# layout.net
KiCad netlist of a schematic drawn in EAGLE
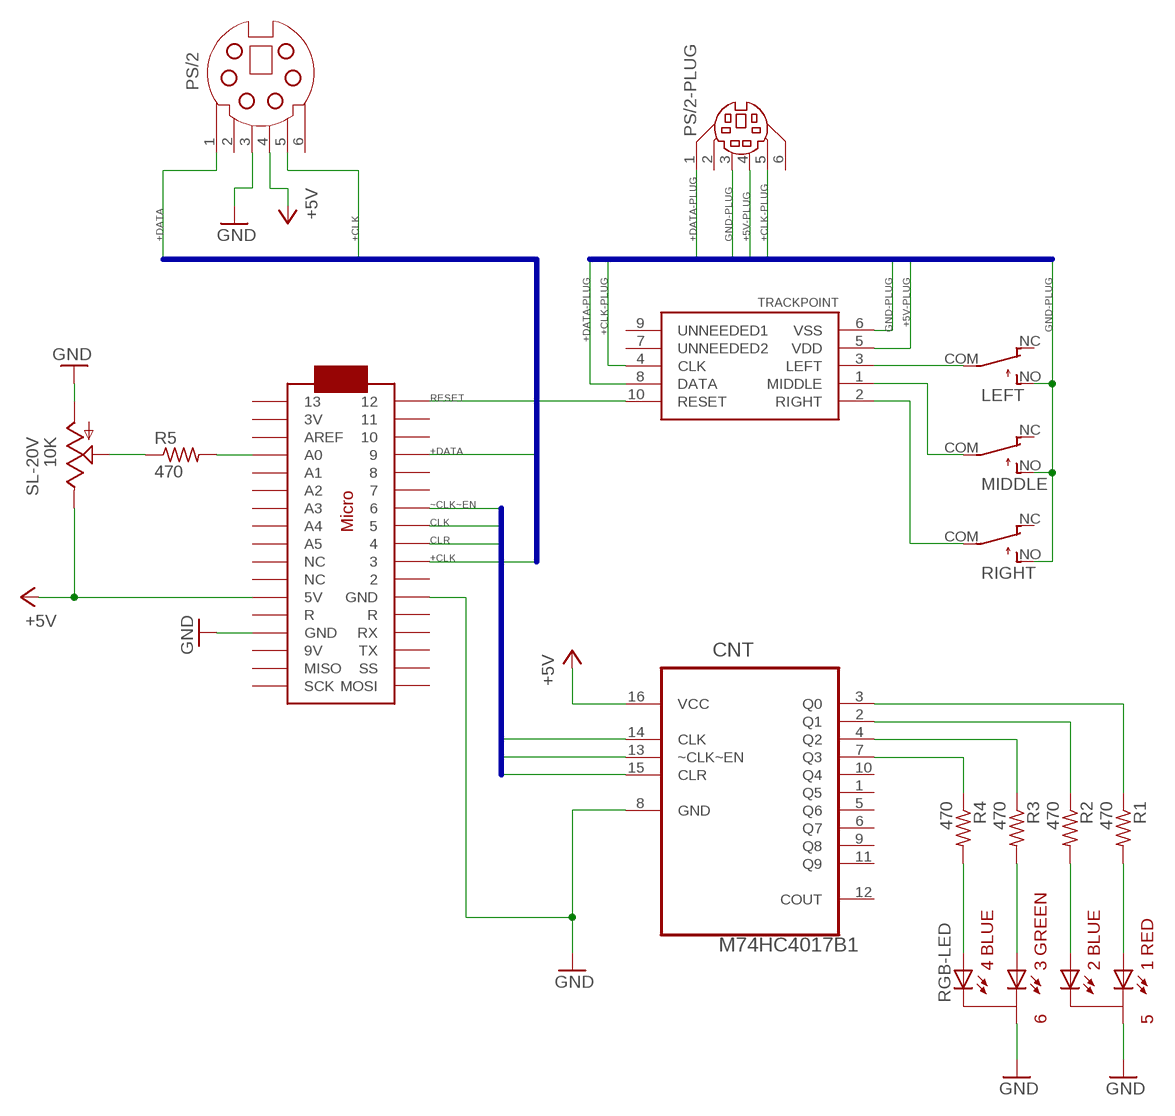
[diagram p0: schematic, sheet 1]

(export (version "E")
  (design (tool "Eeschema 10.0.6"))
  (components
    (comp (ref "CNT")
      (value "M74HC4017B1")
      (footprint "eagle-import:DIP254P762X510-16")
      (fields (field (name "MPN") "M74HC4017B1R"))
      (libsource (lib "eagle-import") (part "M74HC4017B1R"))
    )
    (comp (ref "PS/2")
      (value "MDSSV-BC06")
      (footprint "eagle-import:SSV-BC06")
      (libsource (lib "eagle-import") (part "MDSSV-BC06"))
    )
    (comp (ref "PS/2-PLUG")
      (value "MDIN06K")
      (footprint "eagle-import:MDIN06K")
      (libsource (lib "eagle-import") (part "MDIN06K"))
    )
    (comp (ref "R1")
      (value "470")
      (footprint "eagle-import:0207_10")
      (libsource (lib "eagle-import") (part "R-US_0207/10"))
    )
    (comp (ref "R2")
      (value "470")
      (footprint "eagle-import:0207_10")
      (libsource (lib "eagle-import") (part "R-US_0207/10"))
    )
    (comp (ref "R3")
      (value "470")
      (footprint "eagle-import:0207_10")
      (libsource (lib "eagle-import") (part "R-US_0207/10"))
    )
    (comp (ref "R4")
      (value "470")
      (footprint "eagle-import:0207_10")
      (libsource (lib "eagle-import") (part "R-US_0207/10"))
    )
    (comp (ref "R5")
      (value "470")
      (footprint "eagle-import:0207_10")
      (libsource (lib "eagle-import") (part "R-US_0207/10"))
    )
    (comp (ref "RGB-LED")
      (value "RGBLED")
      (footprint "eagle-import:RGBLED5MM")
      (libsource (lib "eagle-import") (part "RGBLED"))
    )
    (comp (ref "TRACKPOINT")
      (value "BOARD")
      (footprint "eagle-import:BOARD")
      (libsource (lib "eagle-import") (part "BOARD"))
    )
    (comp (ref "U$1")
      (value "LEFT")
      (footprint "eagle-import:D2F")
      (libsource (lib "eagle-import") (part "D2F"))
    )
    (comp (ref "U$2")
      (value "ARDUINOMICRO")
      (footprint "eagle-import:ARDUINOMICRO")
      (libsource (lib "eagle-import") (part "ARDUINOMICRO"))
    )
    (comp (ref "U$3")
      (value "MIDDLE")
      (footprint "eagle-import:D2F")
      (libsource (lib "eagle-import") (part "D2F"))
    )
    (comp (ref "U$5")
      (value "RIGHT")
      (footprint "eagle-import:D2F")
      (libsource (lib "eagle-import") (part "D2F"))
    )
    (comp (ref "U$6")
      (value "10K")
      (footprint "eagle-import:SL-20V")
      (libsource (lib "eagle-import") (part "SL-20V"))
    )
  )
  (nets
    (net (code "1") (name "+5V") (class "Default")
      (node (ref "CNT") (pin "16") (pinfunction "VCC_16") (pintype "power_in"))
      (node (ref "PS/2") (pin "4") (pinfunction "4_4") (pintype "passive"))
      (node (ref "U$2") (pin "P$23") (pinfunction "5V_P$23") (pintype "bidirectional"))
      (node (ref "U$6") (pin "4") (pinfunction "E_4") (pintype "passive"))
    )
    (net (code "2") (name "/+5V-PLUG") (class "Default")
      (node (ref "PS/2-PLUG") (pin "4") (pinfunction "4_4") (pintype "passive"))
      (node (ref "TRACKPOINT") (pin "5") (pinfunction "VDD_5") (pintype "bidirectional"))
    )
    (net (code "3") (name "/+CLK") (class "Default")
      (node (ref "PS/2") (pin "5") (pinfunction "5_5") (pintype "passive"))
      (node (ref "U$2") (pin "P$10") (pinfunction "3_P$10") (pintype "bidirectional"))
    )
    (net (code "4") (name "/+CLK-PLUG") (class "Default")
      (node (ref "PS/2-PLUG") (pin "5") (pinfunction "5_5") (pintype "passive"))
      (node (ref "TRACKPOINT") (pin "4") (pinfunction "CLK_4") (pintype "bidirectional"))
    )
    (net (code "5") (name "/+DATA") (class "Default")
      (node (ref "PS/2") (pin "1") (pinfunction "1_1") (pintype "passive"))
      (node (ref "U$2") (pin "P$4") (pinfunction "9_P$4") (pintype "bidirectional"))
    )
    (net (code "6") (name "/+DATA-PLUG") (class "Default")
      (node (ref "PS/2-PLUG") (pin "1") (pinfunction "1_1") (pintype "passive"))
      (node (ref "TRACKPOINT") (pin "8") (pinfunction "DATA_8") (pintype "bidirectional"))
    )
    (net (code "7") (name "/CLK") (class "Default")
      (node (ref "CNT") (pin "14") (pinfunction "CLK_14") (pintype "input"))
      (node (ref "U$2") (pin "P$8") (pinfunction "5_P$8") (pintype "bidirectional"))
    )
    (net (code "8") (name "/CLR") (class "Default")
      (node (ref "CNT") (pin "15") (pinfunction "CLR_15") (pintype "input"))
      (node (ref "U$2") (pin "P$9") (pinfunction "4_P$9") (pintype "bidirectional"))
    )
    (net (code "9") (name "/GND-PLUG") (class "Default")
      (node (ref "PS/2-PLUG") (pin "3") (pinfunction "3_3") (pintype "passive"))
      (node (ref "TRACKPOINT") (pin "6") (pinfunction "VSS_6") (pintype "bidirectional"))
      (node (ref "U$1") (pin "NO") (pinfunction "S_NO") (pintype "passive"))
      (node (ref "U$3") (pin "NO") (pinfunction "S_NO") (pintype "passive"))
      (node (ref "U$5") (pin "NO") (pinfunction "S_NO") (pintype "passive"))
    )
    (net (code "10") (name "/RESET") (class "Default")
      (node (ref "TRACKPOINT") (pin "10") (pinfunction "RESET_10") (pintype "bidirectional"))
      (node (ref "U$2") (pin "P$1") (pinfunction "12_P$1") (pintype "bidirectional"))
    )
    (net (code "11") (name "/~{CLK}EN") (class "Default")
      (node (ref "CNT") (pin "13") (pinfunction "~{CLK}EN_13") (pintype "input"))
      (node (ref "U$2") (pin "P$7") (pinfunction "6_P$7") (pintype "bidirectional"))
    )
    (net (code "12") (name "GND") (class "Default")
      (node (ref "CNT") (pin "8") (pinfunction "GND_8") (pintype "passive"))
      (node (ref "PS/2") (pin "3") (pinfunction "3_3") (pintype "passive"))
      (node (ref "RGB-LED") (pin "C5") (pinfunction "C5_C5") (pintype "passive"))
      (node (ref "RGB-LED") (pin "C6") (pinfunction "C6_C6") (pintype "passive"))
      (node (ref "U$2") (pin "P$12") (pinfunction "GND_P$12") (pintype "bidirectional"))
      (node (ref "U$2") (pin "P$21") (pinfunction "GND_P$21") (pintype "bidirectional"))
      (node (ref "U$6") (pin "1") (pinfunction "A_1") (pintype "passive"))
    )
    (net (code "13") (name "Net-(CNT-Q0)") (class "Default")
      (node (ref "CNT") (pin "3") (pinfunction "Q0_3") (pintype "output"))
      (node (ref "R1") (pin "1") (pinfunction "1_1") (pintype "passive"))
    )
    (net (code "14") (name "Net-(CNT-Q1)") (class "Default")
      (node (ref "CNT") (pin "2") (pinfunction "Q1_2") (pintype "output"))
      (node (ref "R2") (pin "1") (pinfunction "1_1") (pintype "passive"))
    )
    (net (code "15") (name "Net-(CNT-Q2)") (class "Default")
      (node (ref "CNT") (pin "4") (pinfunction "Q2_4") (pintype "output"))
      (node (ref "R3") (pin "1") (pinfunction "1_1") (pintype "passive"))
    )
    (net (code "16") (name "Net-(CNT-Q3)") (class "Default")
      (node (ref "CNT") (pin "7") (pinfunction "Q3_7") (pintype "output"))
      (node (ref "R4") (pin "1") (pinfunction "1_1") (pintype "passive"))
    )
    (net (code "17") (name "Net-(R1-Pad2)") (class "Default")
      (node (ref "R1") (pin "2") (pinfunction "2_2") (pintype "passive"))
      (node (ref "RGB-LED") (pin "A1_RED") (pinfunction "A1_RED_A1_RED") (pintype "passive"))
    )
    (net (code "18") (name "Net-(R2-Pad2)") (class "Default")
      (node (ref "R2") (pin "2") (pinfunction "2_2") (pintype "passive"))
      (node (ref "RGB-LED") (pin "A2_BLUE") (pinfunction "A2_BLUE_A2_BLUE") (pintype "passive"))
    )
    (net (code "19") (name "Net-(R3-Pad2)") (class "Default")
      (node (ref "R3") (pin "2") (pinfunction "2_2") (pintype "passive"))
      (node (ref "RGB-LED") (pin "A3_GREEN") (pinfunction "A3_GREEN_A3_GREEN") (pintype "passive"))
    )
    (net (code "20") (name "Net-(R4-Pad2)") (class "Default")
      (node (ref "R4") (pin "2") (pinfunction "2_2") (pintype "passive"))
      (node (ref "RGB-LED") (pin "A4_BLUE") (pinfunction "A4_BLUE_A4_BLUE") (pintype "passive"))
    )
    (net (code "21") (name "Net-(R5-Pad1)") (class "Default")
      (node (ref "R5") (pin "1") (pinfunction "1_1") (pintype "passive"))
      (node (ref "U$6") (pin "2") (pinfunction "S_2") (pintype "passive"))
      (node (ref "U$6") (pin "3") (pinfunction "S_3") (pintype "passive"))
    )
    (net (code "22") (name "Net-(TRACKPOINT-LEFT)") (class "Default")
      (node (ref "TRACKPOINT") (pin "3") (pinfunction "LEFT_3") (pintype "bidirectional"))
      (node (ref "U$1") (pin "COM") (pinfunction "P_COM") (pintype "passive"))
    )
    (net (code "23") (name "Net-(TRACKPOINT-MIDDLE)") (class "Default")
      (node (ref "TRACKPOINT") (pin "1") (pinfunction "MIDDLE_1") (pintype "bidirectional"))
      (node (ref "U$3") (pin "COM") (pinfunction "P_COM") (pintype "passive"))
    )
    (net (code "24") (name "Net-(TRACKPOINT-RIGHT)") (class "Default")
      (node (ref "TRACKPOINT") (pin "2") (pinfunction "RIGHT_2") (pintype "bidirectional"))
      (node (ref "U$5") (pin "COM") (pinfunction "P_COM") (pintype "passive"))
    )
    (net (code "25") (name "Net-(U$2-A0)") (class "Default")
      (node (ref "R5") (pin "2") (pinfunction "2_2") (pintype "passive"))
      (node (ref "U$2") (pin "P$31") (pinfunction "A0_P$31") (pintype "bidirectional"))
    )
    (net (code "26") (name "unconnected-(CNT-COUT-Pad12)") (class "Default")
      (node (ref "CNT") (pin "12") (pinfunction "COUT_12") (pintype "output"))
    )
    (net (code "27") (name "unconnected-(CNT-Q4-Pad10)") (class "Default")
      (node (ref "CNT") (pin "10") (pinfunction "Q4_10") (pintype "output"))
    )
    (net (code "28") (name "unconnected-(CNT-Q5-Pad1)") (class "Default")
      (node (ref "CNT") (pin "1") (pinfunction "Q5_1") (pintype "output"))
    )
    (net (code "29") (name "unconnected-(CNT-Q6-Pad5)") (class "Default")
      (node (ref "CNT") (pin "5") (pinfunction "Q6_5") (pintype "output"))
    )
    (net (code "30") (name "unconnected-(CNT-Q7-Pad6)") (class "Default")
      (node (ref "CNT") (pin "6") (pinfunction "Q7_6") (pintype "output"))
    )
    (net (code "31") (name "unconnected-(CNT-Q8-Pad9)") (class "Default")
      (node (ref "CNT") (pin "9") (pinfunction "Q8_9") (pintype "output"))
    )
    (net (code "32") (name "unconnected-(CNT-Q9-Pad11)") (class "Default")
      (node (ref "CNT") (pin "11") (pinfunction "Q9_11") (pintype "output"))
    )
    (net (code "33") (name "unconnected-(PS/2-PLUG-Pad2)") (class "Default")
      (node (ref "PS/2-PLUG") (pin "2") (pinfunction "2_2") (pintype "passive"))
    )
    (net (code "34") (name "unconnected-(PS/2-PLUG-Pad6)") (class "Default")
      (node (ref "PS/2-PLUG") (pin "6") (pinfunction "6_6") (pintype "passive"))
    )
    (net (code "35") (name "unconnected-(PS/2-Pad2)") (class "Default")
      (node (ref "PS/2") (pin "2") (pinfunction "2_2") (pintype "passive"))
    )
    (net (code "36") (name "unconnected-(PS/2-Pad6)") (class "Default")
      (node (ref "PS/2") (pin "6") (pinfunction "6_6") (pintype "passive"))
    )
    (net (code "37") (name "unconnected-(TRACKPOINT-UNNEEDED1-Pad9)") (class "Default")
      (node (ref "TRACKPOINT") (pin "9") (pinfunction "UNNEEDED1_9") (pintype "bidirectional"))
    )
    (net (code "38") (name "unconnected-(TRACKPOINT-UNNEEDED2-Pad7)") (class "Default")
      (node (ref "TRACKPOINT") (pin "7") (pinfunction "UNNEEDED2_7") (pintype "bidirectional"))
    )
    (net (code "39") (name "unconnected-(U$1-O-PadNC)") (class "Default")
      (node (ref "U$1") (pin "NC") (pinfunction "O_NC") (pintype "passive"))
    )
    (net (code "40") (name "unconnected-(U$2-2-PadP$11)") (class "Default")
      (node (ref "U$2") (pin "P$11") (pinfunction "2_P$11") (pintype "bidirectional"))
    )
    (net (code "41") (name "unconnected-(U$2-3V-PadP$33)") (class "Default")
      (node (ref "U$2") (pin "P$33") (pinfunction "3V_P$33") (pintype "bidirectional"))
    )
    (net (code "42") (name "unconnected-(U$2-7-PadP$6)") (class "Default")
      (node (ref "U$2") (pin "P$6") (pinfunction "7_P$6") (pintype "bidirectional"))
    )
    (net (code "43") (name "unconnected-(U$2-8-PadP$5)") (class "Default")
      (node (ref "U$2") (pin "P$5") (pinfunction "8_P$5") (pintype "bidirectional"))
    )
    (net (code "44") (name "unconnected-(U$2-9V-PadP$20)") (class "Default")
      (node (ref "U$2") (pin "P$20") (pinfunction "9V_P$20") (pintype "bidirectional"))
    )
    (net (code "45") (name "unconnected-(U$2-10-PadP$3)") (class "Default")
      (node (ref "U$2") (pin "P$3") (pinfunction "10_P$3") (pintype "bidirectional"))
    )
    (net (code "46") (name "unconnected-(U$2-11-PadP$2)") (class "Default")
      (node (ref "U$2") (pin "P$2") (pinfunction "11_P$2") (pintype "bidirectional"))
    )
    (net (code "47") (name "unconnected-(U$2-13-PadP$34)") (class "Default")
      (node (ref "U$2") (pin "P$34") (pinfunction "13_P$34") (pintype "bidirectional"))
    )
    (net (code "48") (name "unconnected-(U$2-A1-PadP$30)") (class "Default")
      (node (ref "U$2") (pin "P$30") (pinfunction "A1_P$30") (pintype "bidirectional"))
    )
    (net (code "49") (name "unconnected-(U$2-A2-PadP$29)") (class "Default")
      (node (ref "U$2") (pin "P$29") (pinfunction "A2_P$29") (pintype "bidirectional"))
    )
    (net (code "50") (name "unconnected-(U$2-A3-PadP$28)") (class "Default")
      (node (ref "U$2") (pin "P$28") (pinfunction "A3_P$28") (pintype "bidirectional"))
    )
    (net (code "51") (name "unconnected-(U$2-A4-PadP$27)") (class "Default")
      (node (ref "U$2") (pin "P$27") (pinfunction "A4_P$27") (pintype "bidirectional"))
    )
    (net (code "52") (name "unconnected-(U$2-A5-PadP$26)") (class "Default")
      (node (ref "U$2") (pin "P$26") (pinfunction "A5_P$26") (pintype "bidirectional"))
    )
    (net (code "53") (name "unconnected-(U$2-AREF-PadP$32)") (class "Default")
      (node (ref "U$2") (pin "P$32") (pinfunction "AREF_P$32") (pintype "bidirectional"))
    )
    (net (code "54") (name "unconnected-(U$2-MISO-PadP$19)") (class "Default")
      (node (ref "U$2") (pin "P$19") (pinfunction "MISO_P$19") (pintype "bidirectional"))
    )
    (net (code "55") (name "unconnected-(U$2-MOSI-PadP$17)") (class "Default")
      (node (ref "U$2") (pin "P$17") (pinfunction "MOSI_P$17") (pintype "bidirectional"))
    )
    (net (code "56") (name "unconnected-(U$2-NC-PadP$24)") (class "Default")
      (node (ref "U$2") (pin "P$24") (pinfunction "NC_P$24") (pintype "bidirectional"))
    )
    (net (code "57") (name "unconnected-(U$2-NC-PadP$25)") (class "Default")
      (node (ref "U$2") (pin "P$25") (pinfunction "NC_P$25") (pintype "bidirectional"))
    )
    (net (code "58") (name "unconnected-(U$2-R-PadP$13)") (class "Default")
      (node (ref "U$2") (pin "P$13") (pinfunction "R_P$13") (pintype "bidirectional"))
    )
    (net (code "59") (name "unconnected-(U$2-R-PadP$22)") (class "Default")
      (node (ref "U$2") (pin "P$22") (pinfunction "R_P$22") (pintype "bidirectional"))
    )
    (net (code "60") (name "unconnected-(U$2-RX-PadP$14)") (class "Default")
      (node (ref "U$2") (pin "P$14") (pinfunction "RX_P$14") (pintype "bidirectional"))
    )
    (net (code "61") (name "unconnected-(U$2-SCK-PadP$18)") (class "Default")
      (node (ref "U$2") (pin "P$18") (pinfunction "SCK_P$18") (pintype "bidirectional"))
    )
    (net (code "62") (name "unconnected-(U$2-SS-PadP$16)") (class "Default")
      (node (ref "U$2") (pin "P$16") (pinfunction "SS_P$16") (pintype "bidirectional"))
    )
    (net (code "63") (name "unconnected-(U$2-TX-PadP$15)") (class "Default")
      (node (ref "U$2") (pin "P$15") (pinfunction "TX_P$15") (pintype "bidirectional"))
    )
    (net (code "64") (name "unconnected-(U$3-O-PadNC)") (class "Default")
      (node (ref "U$3") (pin "NC") (pinfunction "O_NC") (pintype "passive"))
    )
    (net (code "65") (name "unconnected-(U$5-O-PadNC)") (class "Default")
      (node (ref "U$5") (pin "NC") (pinfunction "O_NC") (pintype "passive"))
    )
  )
)
